# BackupPowerUnit.net
KiCad netlist of a schematic drawn in EAGLE
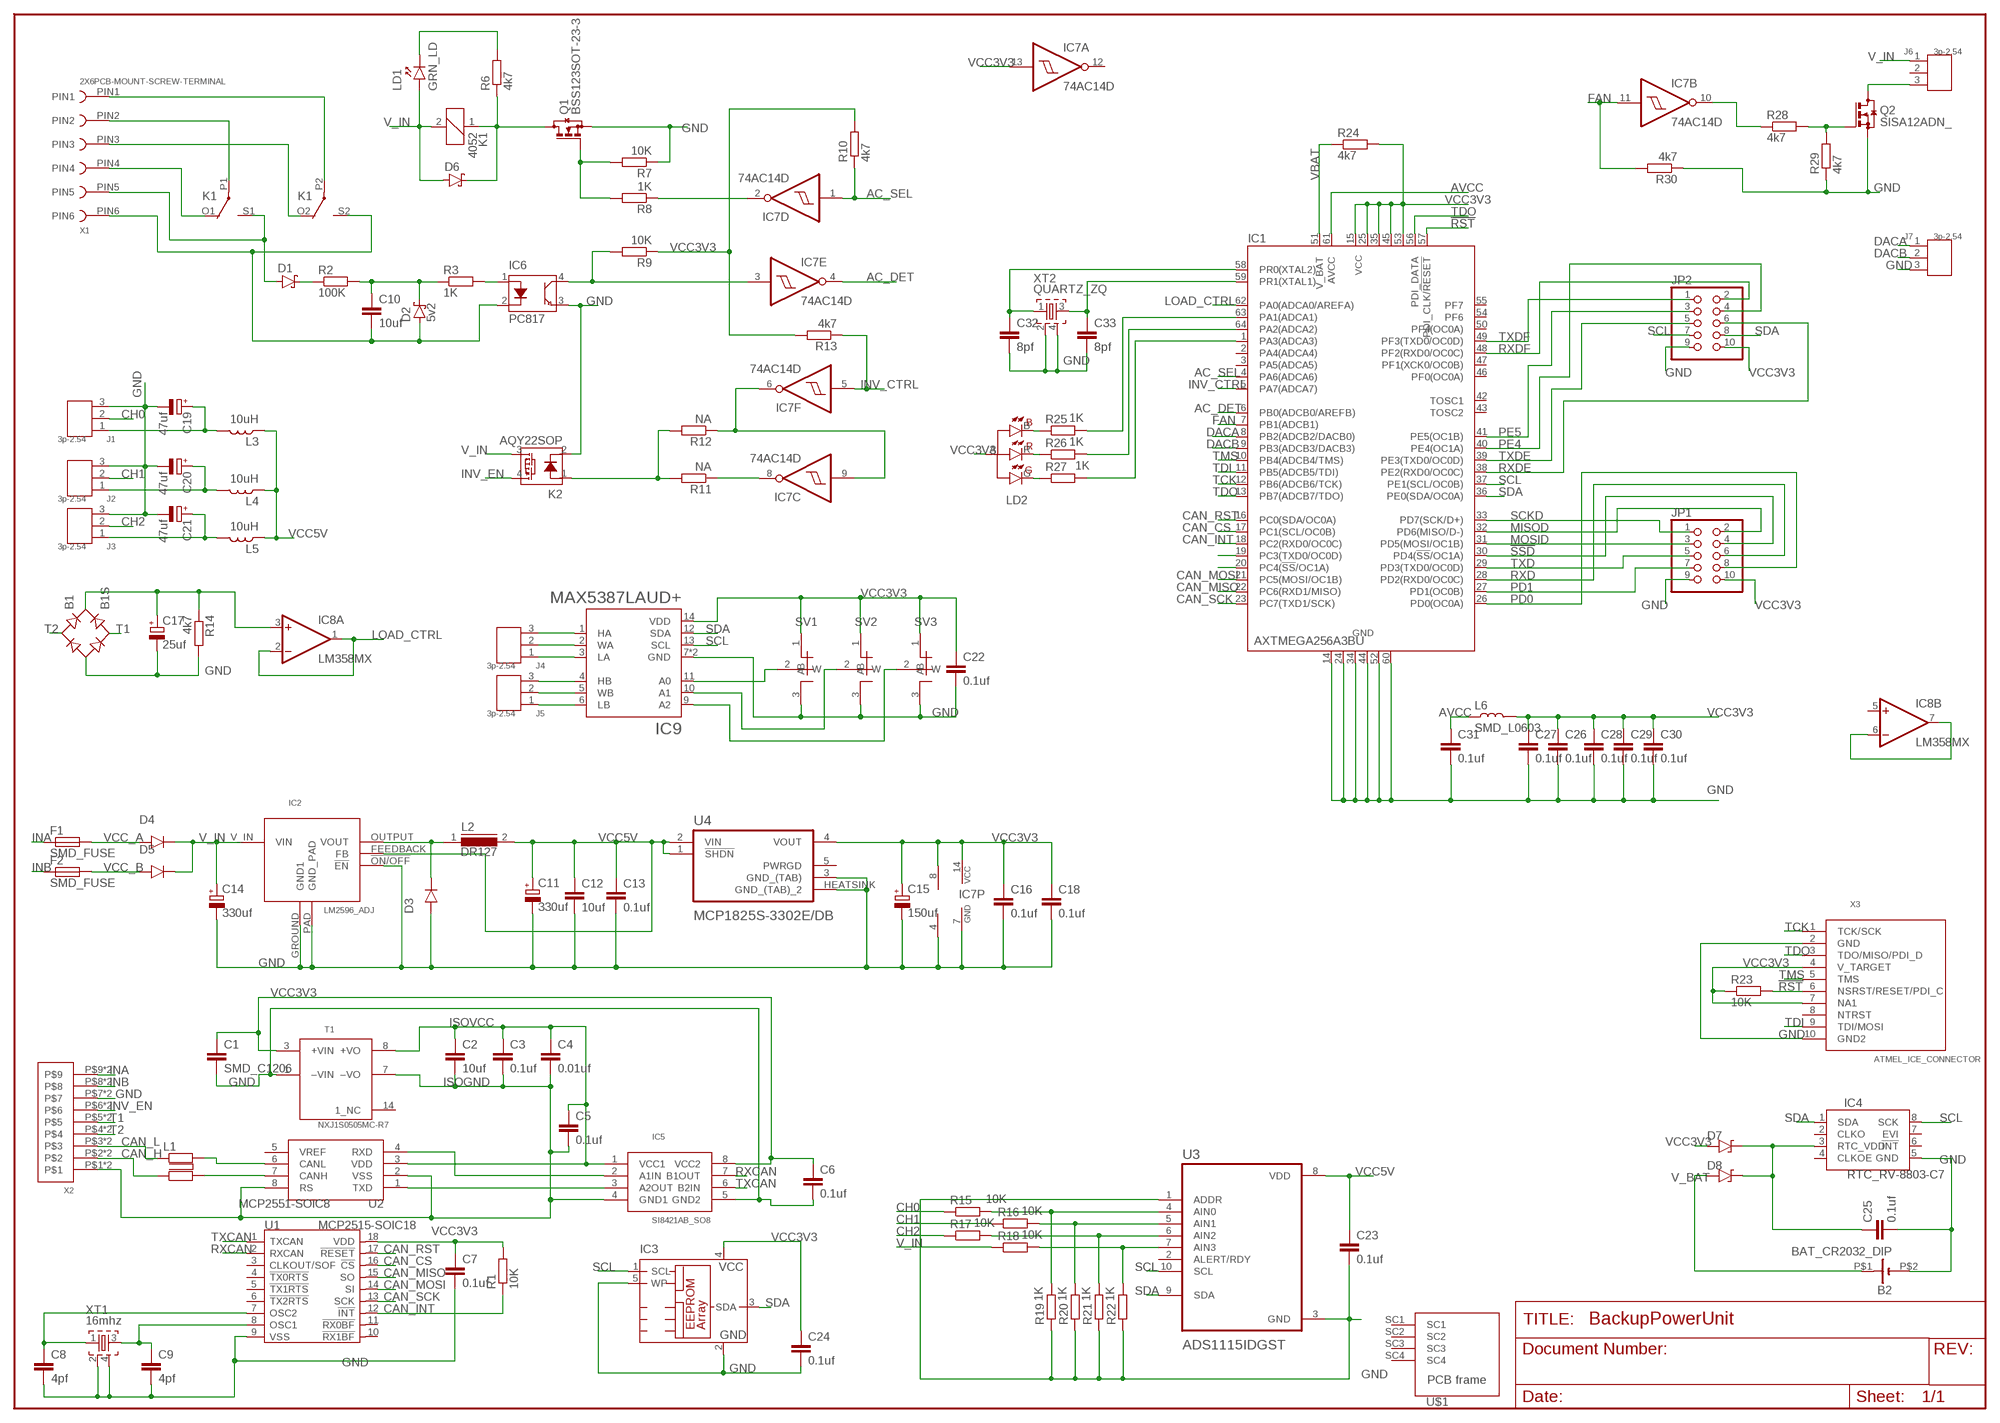
[diagram p0: schematic, sheet 1]

(export (version "E")
  (design (tool "Eeschema 10.0.6"))
  (components
    (comp (ref "B1")
      (value "B1S")
      (footprint "eagle-import:MBS")
      (libsource (lib "eagle-import") (part "BS1"))
    )
    (comp (ref "B2")
      (value "BAT_CR2032_DIP")
      (footprint "eagle-import:CR2032_DIP")
      (libsource (lib "eagle-import") (part "BAT_CR2032_DIP"))
    )
    (comp (ref "C1")
      (value "SMD_C1206")
      (footprint "eagle-import:1206")
      (libsource (lib "eagle-import") (part "SMD_C1206"))
    )
    (comp (ref "C2")
      (value "10uf")
      (footprint "eagle-import:1206")
      (libsource (lib "eagle-import") (part "SMD_C1206"))
    )
    (comp (ref "C3")
      (value "0.1uf")
      (footprint "eagle-import:0603")
      (libsource (lib "eagle-import") (part "SMD_C0603"))
    )
    (comp (ref "C4")
      (value "0.01uf")
      (footprint "eagle-import:0603")
      (libsource (lib "eagle-import") (part "SMD_C0603"))
    )
    (comp (ref "C5")
      (value "0.1uf")
      (footprint "eagle-import:0603")
      (libsource (lib "eagle-import") (part "SMD_C0603"))
    )
    (comp (ref "C6")
      (value "0.1uf")
      (footprint "eagle-import:0603")
      (libsource (lib "eagle-import") (part "SMD_C0603"))
    )
    (comp (ref "C7")
      (value "0.1uf")
      (footprint "eagle-import:0603")
      (libsource (lib "eagle-import") (part "SMD_C0603"))
    )
    (comp (ref "C8")
      (value "4pf")
      (footprint "eagle-import:0603")
      (libsource (lib "eagle-import") (part "SMD_C0603"))
    )
    (comp (ref "C9")
      (value "4pf")
      (footprint "eagle-import:0603")
      (libsource (lib "eagle-import") (part "SMD_C0603"))
    )
    (comp (ref "C10")
      (value "10uf")
      (footprint "eagle-import:0805")
      (libsource (lib "eagle-import") (part "SMD_C0805"))
    )
    (comp (ref "C11")
      (value "330uf")
      (footprint "eagle-import:3.6MM")
      (libsource (lib "eagle-import") (part "RADIAL_330UF_25V_8MM"))
    )
    (comp (ref "C12")
      (value "10uf")
      (footprint "eagle-import:1206")
      (libsource (lib "eagle-import") (part "SMD_C1206"))
    )
    (comp (ref "C13")
      (value "0.1uf")
      (footprint "eagle-import:0603")
      (libsource (lib "eagle-import") (part "SMD_C0603"))
    )
    (comp (ref "C14")
      (value "330uf")
      (footprint "eagle-import:3.6MM")
      (libsource (lib "eagle-import") (part "RADIAL_330UF_25V_8MM"))
    )
    (comp (ref "C15")
      (value "150uf")
      (footprint "eagle-import:KA-3528ASYC")
      (libsource (lib "eagle-import") (part "TANTAL_150UF_3528"))
    )
    (comp (ref "C16")
      (value "0.1uf")
      (footprint "eagle-import:0603")
      (libsource (lib "eagle-import") (part "SMD_C0603"))
    )
    (comp (ref "C17")
      (value "25uf")
      (footprint "eagle-import:KA-3528ASYC")
      (libsource (lib "eagle-import") (part "TANTAL_150UF_3528"))
    )
    (comp (ref "C18")
      (value "0.1uf")
      (footprint "eagle-import:0603")
      (libsource (lib "eagle-import") (part "SMD_C0603"))
    )
    (comp (ref "C19")
      (value "47uf")
      (footprint "eagle-import:KA-3528ASYC")
      (libsource (lib "eagle-import") (part "TANTAL_150UF_3528"))
    )
    (comp (ref "C20")
      (value "47uf")
      (footprint "eagle-import:KA-3528ASYC")
      (libsource (lib "eagle-import") (part "TANTAL_150UF_3528"))
    )
    (comp (ref "C21")
      (value "47uf")
      (footprint "eagle-import:KA-3528ASYC")
      (libsource (lib "eagle-import") (part "TANTAL_150UF_3528"))
    )
    (comp (ref "C22")
      (value "0.1uf")
      (footprint "eagle-import:0603")
      (libsource (lib "eagle-import") (part "SMD_C0603"))
    )
    (comp (ref "C23")
      (value "0.1uf")
      (footprint "eagle-import:0603")
      (libsource (lib "eagle-import") (part "SMD_C0603"))
    )
    (comp (ref "C24")
      (value "0.1uf")
      (footprint "eagle-import:0603")
      (libsource (lib "eagle-import") (part "SMD_C0603"))
    )
    (comp (ref "C25")
      (value "0.1uf")
      (footprint "eagle-import:0603")
      (libsource (lib "eagle-import") (part "SMD_C0603"))
    )
    (comp (ref "C26")
      (value "0.1uf")
      (footprint "eagle-import:0603")
      (libsource (lib "eagle-import") (part "SMD_C0603"))
    )
    (comp (ref "C27")
      (value "0.1uf")
      (footprint "eagle-import:0603")
      (libsource (lib "eagle-import") (part "SMD_C0603"))
    )
    (comp (ref "C28")
      (value "0.1uf")
      (footprint "eagle-import:0603")
      (libsource (lib "eagle-import") (part "SMD_C0603"))
    )
    (comp (ref "C29")
      (value "0.1uf")
      (footprint "eagle-import:0603")
      (libsource (lib "eagle-import") (part "SMD_C0603"))
    )
    (comp (ref "C30")
      (value "0.1uf")
      (footprint "eagle-import:0603")
      (libsource (lib "eagle-import") (part "SMD_C0603"))
    )
    (comp (ref "C31")
      (value "0.1uf")
      (footprint "eagle-import:0603")
      (libsource (lib "eagle-import") (part "SMD_C0603"))
    )
    (comp (ref "C32")
      (value "8pf")
      (footprint "eagle-import:0603")
      (libsource (lib "eagle-import") (part "SMD_C0603"))
    )
    (comp (ref "C33")
      (value "8pf")
      (footprint "eagle-import:0603")
      (libsource (lib "eagle-import") (part "SMD_C0603"))
    )
    (comp (ref "D1")
      (value "1N5819-B")
      (footprint "eagle-import:DO41-7.6")
      (libsource (lib "eagle-import") (part "1N5819-B"))
    )
    (comp (ref "D2")
      (value "5v2")
      (footprint "eagle-import:DO41-7.6")
      (libsource (lib "eagle-import") (part "1N5819-B"))
    )
    (comp (ref "D3")
      (value "D_MBRA340G")
      (footprint "eagle-import:SMA403D")
      (libsource (lib "eagle-import") (part "D_MBRA340G"))
    )
    (comp (ref "D4")
      (value "D_MBRA340G")
      (footprint "eagle-import:SMA403D")
      (libsource (lib "eagle-import") (part "D_MBRA340G"))
    )
    (comp (ref "D5")
      (value "D_MBRA340G")
      (footprint "eagle-import:SMA403D")
      (libsource (lib "eagle-import") (part "D_MBRA340G"))
    )
    (comp (ref "D6")
      (value "1N5819-B")
      (footprint "eagle-import:DO41-7.6")
      (libsource (lib "eagle-import") (part "1N5819-B"))
    )
    (comp (ref "D7")
      (value "D_SOD323")
      (footprint "eagle-import:SOD-323_D")
      (libsource (lib "eagle-import") (part "D_SOD323"))
    )
    (comp (ref "D8")
      (value "D_SOD323")
      (footprint "eagle-import:SOD-323_D")
      (libsource (lib "eagle-import") (part "D_SOD323"))
    )
    (comp (ref "F1")
      (value "SMD_FUSE")
      (footprint "eagle-import:SMD_2410_FUSE_NOK")
      (libsource (lib "eagle-import") (part "SMD_FUSE"))
    )
    (comp (ref "F2")
      (value "SMD_FUSE")
      (footprint "eagle-import:SMD_2410_FUSE_NOK")
      (libsource (lib "eagle-import") (part "SMD_FUSE"))
    )
    (comp (ref "IC1")
      (value "AXTMEGA256A3BU")
      (footprint "eagle-import:TQFP64")
      (libsource (lib "eagle-import") (part "AXTMEGA256A3BU"))
    )
    (comp (ref "IC2")
      (value "LM2596_ADJ")
      (footprint "eagle-import:DDPAK_TO-263(S)")
      (libsource (lib "eagle-import") (part "LM2596_ADJ"))
    )
    (comp (ref "IC3")
      (value "MICROCHIP-24AA01T-I/OT")
      (footprint "eagle-import:SOT-23(5)")
      (libsource (lib "eagle-import") (part "MICROCHIP-24AA01T-I/OT"))
    )
    (comp (ref "IC4")
      (value "RTC_RV-8803-C7")
      (footprint "eagle-import:C7_RTC")
      (libsource (lib "eagle-import") (part "RTC_RV-8803-C7"))
    )
    (comp (ref "IC5")
      (value "SI8421AB_SO8")
      (footprint "eagle-import:SO8")
      (libsource (lib "eagle-import") (part "SI8421AB_SO8"))
    )
    (comp (ref "IC6")
      (value "PC817")
      (footprint "eagle-import:DIL4-SMD")
      (libsource (lib "eagle-import") (part "PC817"))
    )
    (comp (ref "IC7")
      (value "74AC14D")
      (footprint "eagle-import:SO14")
      (libsource (lib "eagle-import") (part "7414DAC"))
    )
    (comp (ref "IC8")
      (value "LM358MX")
      (footprint "eagle-import:SO08")
      (libsource (lib "eagle-import") (part "LM358MX"))
    )
    (comp (ref "IC9")
      (value "MAX5387LAUD+")
      (footprint "eagle-import:SOP65P640X110-14N")
      (libsource (lib "eagle-import") (part "MAX5387LAUD+"))
    )
    (comp (ref "J1")
      (value "3p-2.54")
      (footprint "eagle-import:H3-2.54-7.62X5.8MM")
      (fields (field (name "MPN") "MC34631"))
      (libsource (lib "eagle-import") (part "DIP-MALE-JST(3P-2.54)"))
    )
    (comp (ref "J2")
      (value "3p-2.54")
      (footprint "eagle-import:H3-2.54-7.62X5.8MM")
      (fields (field (name "MPN") "MC34631"))
      (libsource (lib "eagle-import") (part "DIP-MALE-JST(3P-2.54)"))
    )
    (comp (ref "J3")
      (value "3p-2.54")
      (footprint "eagle-import:H3-2.54-7.62X5.8MM")
      (fields (field (name "MPN") "MC34631"))
      (libsource (lib "eagle-import") (part "DIP-MALE-JST(3P-2.54)"))
    )
    (comp (ref "J4")
      (value "3p-2.54")
      (footprint "eagle-import:H3-2.54-7.62X5.8MM")
      (fields (field (name "MPN") "MC34631"))
      (libsource (lib "eagle-import") (part "DIP-MALE-JST(3P-2.54)"))
    )
    (comp (ref "J5")
      (value "3p-2.54")
      (footprint "eagle-import:H3-2.54-7.62X5.8MM")
      (fields (field (name "MPN") "MC34631"))
      (libsource (lib "eagle-import") (part "DIP-MALE-JST(3P-2.54)"))
    )
    (comp (ref "J6")
      (value "3p-2.54")
      (footprint "eagle-import:H3-2.54-7.62X5.8MM")
      (fields (field (name "MPN") "MC34631"))
      (libsource (lib "eagle-import") (part "DIP-MALE-JST(3P-2.54)"))
    )
    (comp (ref "J7")
      (value "3p-2.54")
      (footprint "eagle-import:H3-2.54-7.62X5.8MM")
      (fields (field (name "MPN") "MC34631"))
      (libsource (lib "eagle-import") (part "DIP-MALE-JST(3P-2.54)"))
    )
    (comp (ref "JP1")
      (value "PINHD-2X5")
      (footprint "eagle-import:2X05")
      (libsource (lib "eagle-import") (part "PINHD-2X5"))
    )
    (comp (ref "JP2")
      (value "PINHD-2X5")
      (footprint "eagle-import:2X05")
      (libsource (lib "eagle-import") (part "PINHD-2X5"))
    )
    (comp (ref "K1")
      (value "4052")
      (footprint "eagle-import:F4052")
      (libsource (lib "eagle-import") (part "4052"))
    )
    (comp (ref "K2")
      (value "AQY22SOP")
      (footprint "eagle-import:SOP04")
      (libsource (lib "eagle-import") (part "AQYSOP22"))
    )
    (comp (ref "L1")
      (value "EPCOS_B82793_FILTER")
      (footprint "eagle-import:EPCOS_FILTER")
      (libsource (lib "eagle-import") (part "EPCOS_B82793_FILTER"))
    )
    (comp (ref "L2")
      (value "DR127")
      (footprint "eagle-import:DR127")
      (libsource (lib "eagle-import") (part "DR127"))
    )
    (comp (ref "L3")
      (value "10uH")
      (footprint "eagle-import:0603")
      (libsource (lib "eagle-import") (part "SMD_L0603"))
    )
    (comp (ref "L4")
      (value "10uH")
      (footprint "eagle-import:0603")
      (libsource (lib "eagle-import") (part "SMD_L0603"))
    )
    (comp (ref "L5")
      (value "10uH")
      (footprint "eagle-import:0603")
      (libsource (lib "eagle-import") (part "SMD_L0603"))
    )
    (comp (ref "L6")
      (value "SMD_L0603")
      (footprint "eagle-import:0603")
      (libsource (lib "eagle-import") (part "SMD_L0603"))
    )
    (comp (ref "LD1")
      (value "GRN_LD")
      (footprint "eagle-import:0603_P")
      (libsource (lib "eagle-import") (part "LED0603"))
    )
    (comp (ref "LD2")
      (value "LTSN-N213EGBW(RGB_LED)")
      (footprint "eagle-import:LTSN-N213EGBW")
      (libsource (lib "eagle-import") (part "LTSN-N213EGBW(RGB_LED)"))
    )
    (comp (ref "Q1")
      (value "BSS123SOT-23-3")
      (footprint "eagle-import:SOT-23(3)")
      (libsource (lib "eagle-import") (part "BSS123SOT-23-3"))
    )
    (comp (ref "Q2")
      (value "SISA12ADN_")
      (footprint "eagle-import:VISHAY_SIS468DN-T1-GE3")
      (libsource (lib "eagle-import") (part "SISA12ADN_"))
    )
    (comp (ref "R1")
      (value "10K")
      (footprint "eagle-import:0603")
      (libsource (lib "eagle-import") (part "SMD_R0603"))
    )
    (comp (ref "R2")
      (value "100K")
      (footprint "eagle-import:0204_7")
      (libsource (lib "eagle-import") (part "R-EU_0204/7"))
    )
    (comp (ref "R3")
      (value "1K")
      (footprint "eagle-import:0603")
      (libsource (lib "eagle-import") (part "SMD_R0603"))
    )
    (comp (ref "R6")
      (value "4k7")
      (footprint "eagle-import:0603")
      (libsource (lib "eagle-import") (part "SMD_R0603"))
    )
    (comp (ref "R7")
      (value "10K")
      (footprint "eagle-import:0603")
      (libsource (lib "eagle-import") (part "SMD_R0603"))
    )
    (comp (ref "R8")
      (value "1K")
      (footprint "eagle-import:0603")
      (libsource (lib "eagle-import") (part "SMD_R0603"))
    )
    (comp (ref "R9")
      (value "10K")
      (footprint "eagle-import:0603")
      (libsource (lib "eagle-import") (part "SMD_R0603"))
    )
    (comp (ref "R10")
      (value "4k7")
      (footprint "eagle-import:0603")
      (libsource (lib "eagle-import") (part "SMD_R0603"))
    )
    (comp (ref "R11")
      (value "NA")
      (footprint "eagle-import:0603")
      (libsource (lib "eagle-import") (part "SMD_R0603"))
    )
    (comp (ref "R12")
      (value "NA")
      (footprint "eagle-import:0603")
      (libsource (lib "eagle-import") (part "SMD_R0603"))
    )
    (comp (ref "R13")
      (value "4k7")
      (footprint "eagle-import:0603")
      (libsource (lib "eagle-import") (part "SMD_R0603"))
    )
    (comp (ref "R14")
      (value "4k7")
      (footprint "eagle-import:0603")
      (libsource (lib "eagle-import") (part "SMD_R0603"))
    )
    (comp (ref "R15")
      (value "10K")
      (footprint "eagle-import:0603")
      (libsource (lib "eagle-import") (part "SMD_R0603"))
    )
    (comp (ref "R16")
      (value "10K")
      (footprint "eagle-import:0603")
      (libsource (lib "eagle-import") (part "SMD_R0603"))
    )
    (comp (ref "R17")
      (value "10K")
      (footprint "eagle-import:0603")
      (libsource (lib "eagle-import") (part "SMD_R0603"))
    )
    (comp (ref "R18")
      (value "10K")
      (footprint "eagle-import:0603")
      (libsource (lib "eagle-import") (part "SMD_R0603"))
    )
    (comp (ref "R19")
      (value "1K")
      (footprint "eagle-import:0603")
      (libsource (lib "eagle-import") (part "SMD_R0603"))
    )
    (comp (ref "R20")
      (value "1K")
      (footprint "eagle-import:0603")
      (libsource (lib "eagle-import") (part "SMD_R0603"))
    )
    (comp (ref "R21")
      (value "1K")
      (footprint "eagle-import:0603")
      (libsource (lib "eagle-import") (part "SMD_R0603"))
    )
    (comp (ref "R22")
      (value "1K")
      (footprint "eagle-import:0603")
      (libsource (lib "eagle-import") (part "SMD_R0603"))
    )
    (comp (ref "R23")
      (value "10K")
      (footprint "eagle-import:0603")
      (libsource (lib "eagle-import") (part "SMD_R0603"))
    )
    (comp (ref "R24")
      (value "4k7")
      (footprint "eagle-import:0603")
      (libsource (lib "eagle-import") (part "SMD_R0603"))
    )
    (comp (ref "R25")
      (value "1K")
      (footprint "eagle-import:0603")
      (libsource (lib "eagle-import") (part "SMD_R0603"))
    )
    (comp (ref "R26")
      (value "1K")
      (footprint "eagle-import:0603")
      (libsource (lib "eagle-import") (part "SMD_R0603"))
    )
    (comp (ref "R27")
      (value "1K")
      (footprint "eagle-import:0603")
      (libsource (lib "eagle-import") (part "SMD_R0603"))
    )
    (comp (ref "R28")
      (value "4k7")
      (footprint "eagle-import:0603")
      (libsource (lib "eagle-import") (part "SMD_R0603"))
    )
    (comp (ref "R29")
      (value "4k7")
      (footprint "eagle-import:0603")
      (libsource (lib "eagle-import") (part "SMD_R0603"))
    )
    (comp (ref "R30")
      (value "4k7")
      (footprint "eagle-import:0603")
      (libsource (lib "eagle-import") (part "SMD_R0603"))
    )
    (comp (ref "SV1")
      (value "SMD_SWITCH_JUMPER")
      (footprint "eagle-import:0603_JUMP")
      (libsource (lib "eagle-import") (part "SMD_SWITCH_JUMPER"))
    )
    (comp (ref "SV2")
      (value "SMD_SWITCH_JUMPER")
      (footprint "eagle-import:0603_JUMP")
      (libsource (lib "eagle-import") (part "SMD_SWITCH_JUMPER"))
    )
    (comp (ref "SV3")
      (value "SMD_SWITCH_JUMPER")
      (footprint "eagle-import:0603_JUMP")
      (libsource (lib "eagle-import") (part "SMD_SWITCH_JUMPER"))
    )
    (comp (ref "T1")
      (value "NXJ1S0505MC-R7")
      (footprint "eagle-import:NXJ1SXXXXMC")
      (libsource (lib "eagle-import") (part "NXJ1S0505MC-R7"))
    )
    (comp (ref "U$1")
      (value "JLC_PCB_FRAME80X100_FRAME")
      (footprint "eagle-import:80X100_PCB_FRAME")
      (libsource (lib "eagle-import") (part "JLC_PCB_FRAME80X100_FRAME"))
    )
    (comp (ref "U1")
      (value "MCP2515-SOIC18")
      (footprint "eagle-import:SO18L")
      (libsource (lib "eagle-import") (part "MCP2515-SOIC18"))
    )
    (comp (ref "U2")
      (value "MCP2551-SOIC8")
      (footprint "eagle-import:SO8")
      (libsource (lib "eagle-import") (part "MCP2551-SOIC8"))
    )
    (comp (ref "U3")
      (value "ADS1115IDGST")
      (footprint "eagle-import:SOP50P490X110-10N")
      (fields (field (name "MF") "Texas Instruments"))
      (libsource (lib "eagle-import") (part "ADS1115IDGST"))
    )
    (comp (ref "U4")
      (value "MCP1825S-3302E/DB")
      (footprint "eagle-import:SOT230P700X180-4N")
      (fields (field (name "MF") "Microchip"))
      (libsource (lib "eagle-import") (part "MCP1825S-3302E/DB"))
    )
    (comp (ref "X1")
      (value "2X6PCB-MOUNT-SCREW-TERMINAL")
      (footprint "eagle-import:2X6PCB-MOUNT-SCREW-TERMINAL")
      (libsource (lib "eagle-import") (part "2X6PCB-MOUNT-SCREW-TERMINAL"))
    )
    (comp (ref "X2")
      (value "WAGO250_X9")
      (footprint "eagle-import:WAGO250_FP_9X")
      (libsource (lib "eagle-import") (part "WAGO250_X9"))
    )
    (comp (ref "X3")
      (value "ATMEL_ICE_CONNECTOR")
      (footprint "eagle-import:MINI10P_SPI_JTAG_PDI")
      (libsource (lib "eagle-import") (part "ATMEL_ICE_CONNECTOR"))
    )
    (comp (ref "XT1")
      (value "16mhz")
      (footprint "eagle-import:QUARTZ_3X3MM")
      (libsource (lib "eagle-import") (part "QUARTZ_ZQ"))
    )
    (comp (ref "XT2")
      (value "QUARTZ_ZQ")
      (footprint "eagle-import:QUARTZ_3X3MM")
      (libsource (lib "eagle-import") (part "QUARTZ_ZQ"))
    )
  )
  (nets
    (net (code "1") (name "/AC_DET") (class "Default")
      (node (ref "IC1") (pin "6") (pinfunction "PB0(ADCB0/AREFB)_6") (pintype "bidirectional"))
      (node (ref "IC7") (pin "4") (pinfunction "O_4") (pintype "output"))
    )
    (net (code "2") (name "/AC_SEL") (class "Default")
      (node (ref "IC1") (pin "4") (pinfunction "PA6(ADCA6)_4") (pintype "bidirectional"))
      (node (ref "IC7") (pin "1") (pinfunction "I_1") (pintype "input"))
      (node (ref "R10") (pin "1") (pinfunction "1_1") (pintype "passive"))
    )
    (net (code "3") (name "/AVCC") (class "Default")
      (node (ref "C31") (pin "1") (pinfunction "1_1") (pintype "passive"))
      (node (ref "IC1") (pin "61") (pinfunction "AVCC_61") (pintype "input"))
      (node (ref "L6") (pin "1") (pinfunction "1_1") (pintype "passive"))
    )
    (net (code "4") (name "/CAN_CS") (class "Default")
      (node (ref "IC1") (pin "17") (pinfunction "PC1(SCL/OC0B)_17") (pintype "bidirectional"))
      (node (ref "U1") (pin "16") (pinfunction "~{CS}_16") (pintype "input"))
    )
    (net (code "5") (name "/CAN_H") (class "Default")
      (node (ref "L1") (pin "P$2") (pinfunction "2_P$2") (pintype "passive"))
      (node (ref "X2") (pin "P$2") (pinfunction "P$2_P$2") (pintype "bidirectional"))
      (node (ref "X2") (pin "U$2") (pinfunction "P$2_U$2") (pintype "bidirectional"))
    )
    (net (code "6") (name "/CAN_INT") (class "Default")
      (node (ref "IC1") (pin "18") (pinfunction "PC2(RXD0/OC0C)_18") (pintype "bidirectional"))
      (node (ref "R1") (pin "1") (pinfunction "1_1") (pintype "passive"))
      (node (ref "U1") (pin "12") (pinfunction "~{INT}_12") (pintype "output"))
    )
    (net (code "7") (name "/CAN_L") (class "Default")
      (node (ref "L1") (pin "P$1") (pinfunction "1_P$1") (pintype "passive"))
      (node (ref "X2") (pin "P$3") (pinfunction "P$3_P$3") (pintype "bidirectional"))
      (node (ref "X2") (pin "U$3") (pinfunction "P$3_U$3") (pintype "bidirectional"))
    )
    (net (code "8") (name "/CAN_MISO") (class "Default")
      (node (ref "IC1") (pin "22") (pinfunction "PC6(RXD1/MISO)_22") (pintype "bidirectional"))
      (node (ref "U1") (pin "15") (pinfunction "SO_15") (pintype "output"))
    )
    (net (code "9") (name "/CAN_MOSI") (class "Default")
      (node (ref "IC1") (pin "21") (pinfunction "PC5(MOSI/OC1B)_21") (pintype "bidirectional"))
      (node (ref "U1") (pin "14") (pinfunction "SI_14") (pintype "input"))
    )
    (net (code "10") (name "/CAN_RST") (class "Default")
      (node (ref "IC1") (pin "16") (pinfunction "PC0(SDA/OC0A)_16") (pintype "bidirectional"))
      (node (ref "U1") (pin "17") (pinfunction "~{RESET}_17") (pintype "input"))
    )
    (net (code "11") (name "/CAN_SCK") (class "Default")
      (node (ref "IC1") (pin "23") (pinfunction "PC7(TXD1/SCK)_23") (pintype "bidirectional"))
      (node (ref "U1") (pin "13") (pinfunction "SCK_13") (pintype "input"))
    )
    (net (code "12") (name "/CH0") (class "Default")
      (node (ref "J1") (pin "2") (pinfunction "P$2_2") (pintype "bidirectional"))
      (node (ref "R15") (pin "1") (pinfunction "1_1") (pintype "passive"))
    )
    (net (code "13") (name "/CH1") (class "Default")
      (node (ref "J2") (pin "2") (pinfunction "P$2_2") (pintype "bidirectional"))
      (node (ref "R16") (pin "1") (pinfunction "1_1") (pintype "passive"))
    )
    (net (code "14") (name "/CH2") (class "Default")
      (node (ref "J3") (pin "2") (pinfunction "P$2_2") (pintype "bidirectional"))
      (node (ref "R17") (pin "1") (pinfunction "1_1") (pintype "passive"))
    )
    (net (code "15") (name "/DACA") (class "Default")
      (node (ref "IC1") (pin "8") (pinfunction "PB2(ADCB2/DACB0)_8") (pintype "bidirectional"))
      (node (ref "J7") (pin "1") (pinfunction "P$1_1") (pintype "bidirectional"))
    )
    (net (code "16") (name "/DACB") (class "Default")
      (node (ref "IC1") (pin "9") (pinfunction "PB3(ADCB3/DACB3)_9") (pintype "bidirectional"))
      (node (ref "J7") (pin "2") (pinfunction "P$2_2") (pintype "bidirectional"))
    )
    (net (code "17") (name "/FAN") (class "Default")
      (node (ref "IC1") (pin "7") (pinfunction "PB1(ADCB1)_7") (pintype "bidirectional"))
      (node (ref "IC7") (pin "11") (pinfunction "I_11") (pintype "input"))
      (node (ref "R30") (pin "2") (pinfunction "2_2") (pintype "passive"))
    )
    (net (code "18") (name "/GND") (class "Default")
      (node (ref "B1") (pin "-") (pinfunction "-_-") (pintype "passive"))
      (node (ref "B2") (pin "P$2") (pinfunction "-_P$2") (pintype "passive"))
      (node (ref "C1") (pin "2") (pinfunction "2_2") (pintype "passive"))
      (node (ref "C11") (pin "P$1") (pinfunction "-_P$1") (pintype "passive"))
      (node (ref "C12") (pin "2") (pinfunction "2_2") (pintype "passive"))
      (node (ref "C13") (pin "2") (pinfunction "2_2") (pintype "passive"))
      (node (ref "C14") (pin "P$1") (pinfunction "-_P$1") (pintype "passive"))
      (node (ref "C15") (pin "M") (pinfunction "-_M") (pintype "passive"))
      (node (ref "C16") (pin "2") (pinfunction "2_2") (pintype "passive"))
      (node (ref "C17") (pin "M") (pinfunction "-_M") (pintype "passive"))
      (node (ref "C18") (pin "2") (pinfunction "2_2") (pintype "passive"))
      (node (ref "C19") (pin "M") (pinfunction "-_M") (pintype "passive"))
      (node (ref "C20") (pin "M") (pinfunction "-_M") (pintype "passive"))
      (node (ref "C21") (pin "M") (pinfunction "-_M") (pintype "passive"))
      (node (ref "C22") (pin "2") (pinfunction "2_2") (pintype "passive"))
      (node (ref "C23") (pin "2") (pinfunction "2_2") (pintype "passive"))
      (node (ref "C24") (pin "2") (pinfunction "2_2") (pintype "passive"))
      (node (ref "C25") (pin "2") (pinfunction "2_2") (pintype "passive"))
      (node (ref "C26") (pin "2") (pinfunction "2_2") (pintype "passive"))
      (node (ref "C27") (pin "2") (pinfunction "2_2") (pintype "passive"))
      (node (ref "C28") (pin "2") (pinfunction "2_2") (pintype "passive"))
      (node (ref "C29") (pin "2") (pinfunction "2_2") (pintype "passive"))
      (node (ref "C30") (pin "2") (pinfunction "2_2") (pintype "passive"))
      (node (ref "C31") (pin "2") (pinfunction "2_2") (pintype "passive"))
      (node (ref "C32") (pin "2") (pinfunction "2_2") (pintype "passive"))
      (node (ref "C33") (pin "2") (pinfunction "2_2") (pintype "passive"))
      (node (ref "C6") (pin "2") (pinfunction "2_2") (pintype "passive"))
      (node (ref "C7") (pin "2") (pinfunction "2_2") (pintype "passive"))
      (node (ref "C8") (pin "2") (pinfunction "2_2") (pintype "passive"))
      (node (ref "C9") (pin "2") (pinfunction "2_2") (pintype "passive"))
      (node (ref "D3") (pin "P$2") (pinfunction "A_P$2") (pintype "bidirectional"))
      (node (ref "IC1") (pin "14") (pinfunction "GND1_14") (pintype "power_in"))
      (node (ref "IC1") (pin "24") (pinfunction "GND2_24") (pintype "power_in"))
      (node (ref "IC1") (pin "34") (pinfunction "GND3_34") (pintype "power_in"))
      (node (ref "IC1") (pin "44") (pinfunction "GND4_44") (pintype "power_in"))
      (node (ref "IC1") (pin "52") (pinfunction "GND5_52") (pintype "power_in"))
      (node (ref "IC1") (pin "60") (pinfunction "GND6_60") (pintype "power_in"))
      (node (ref "IC2") (pin "!ON/OFF") (pinfunction "~{EN}_!ON/OFF") (pintype "input"))
      (node (ref "IC2") (pin "GROUND") (pinfunction "GND1_GROUND") (pintype "power_in"))
      (node (ref "IC2") (pin "PAD") (pinfunction "GND_PAD_PAD") (pintype "power_in"))
      (node (ref "IC3") (pin "2") (pinfunction "GND_2") (pintype "power_in"))
      (node (ref "IC3") (pin "5") (pinfunction "WP_5") (pintype "input"))
      (node (ref "IC4") (pin "5") (pinfunction "GND_5") (pintype "bidirectional"))
      (node (ref "IC5") (pin "5") (pinfunction "GND2_5") (pintype "bidirectional"))
      (node (ref "IC6") (pin "3") (pinfunction "E_3") (pintype "passive"))
      (node (ref "IC7") (pin "7") (pinfunction "GND_7") (pintype "power_in"))
      (node (ref "IC8") (pin "4") (pinfunction "V-_4") (pintype "power_in"))
      (node (ref "IC9") (pin "7") (pinfunction "GND_7") (pintype "bidirectional"))
      (node (ref "IC9") (pin "8") (pinfunction "GND_8") (pintype "bidirectional"))
      (node (ref "J1") (pin "3") (pinfunction "P$3_3") (pintype "bidirectional"))
      (node (ref "J2") (pin "3") (pinfunction "P$3_3") (pintype "bidirectional"))
      (node (ref "J3") (pin "3") (pinfunction "P$3_3") (pintype "bidirectional"))
      (node (ref "J7") (pin "3") (pinfunction "P$3_3") (pintype "bidirectional"))
      (node (ref "JP1") (pin "9") (pinfunction "9_9") (pintype "passive"))
      (node (ref "JP2") (pin "9") (pinfunction "9_9") (pintype "passive"))
      (node (ref "K2") (pin "2") (pinfunction "K_2") (pintype "passive"))
      (node (ref "Q1") (pin "2") (pinfunction "S_2") (pintype "passive"))
      (node (ref "Q2") (pin "1") (pinfunction "S_1") (pintype "passive"))
      (node (ref "Q2") (pin "2") (pinfunction "S_2") (pintype "passive"))
      (node (ref "Q2") (pin "3") (pinfunction "S_3") (pintype "passive"))
      (node (ref "R14") (pin "2") (pinfunction "2_2") (pintype "passive"))
      (node (ref "R19") (pin "1") (pinfunction "1_1") (pintype "passive"))
      (node (ref "R20") (pin "1") (pinfunction "1_1") (pintype "passive"))
      (node (ref "R21") (pin "1") (pinfunction "1_1") (pintype "passive"))
      (node (ref "R22") (pin "1") (pinfunction "1_1") (pintype "passive"))
      (node (ref "R29") (pin "1") (pinfunction "1_1") (pintype "passive"))
      (node (ref "R30") (pin "1") (pinfunction "1_1") (pintype "passive"))
      (node (ref "R7") (pin "1") (pinfunction "1_1") (pintype "passive"))
      (node (ref "SV1") (pin "3") (pinfunction "B_3") (pintype "bidirectional"))
      (node (ref "SV2") (pin "3") (pinfunction "B_3") (pintype "bidirectional"))
      (node (ref "SV3") (pin "3") (pinfunction "B_3") (pintype "bidirectional"))
      (node (ref "T1") (pin "1") (pinfunction "–VIN_1") (pintype "power_in"))
      (node (ref "U1") (pin "9") (pinfunction "VSS_9") (pintype "power_in"))
      (node (ref "U3") (pin "1") (pinfunction "ADDR_1") (pintype "input"))
      (node (ref "U3") (pin "3") (pinfunction "GND_3") (pintype "power_in"))
      (node (ref "U4") (pin "3") (pinfunction "GND_(TAB)_3") (pintype "power_in"))
      (node (ref "U4") (pin "HEATSINK") (pinfunction "GND_(TAB)_2_HEATSINK") (pintype "power_in"))
      (node (ref "X2") (pin "P$7") (pinfunction "P$7_P$7") (pintype "bidirectional"))
      (node (ref "X2") (pin "U$7") (pinfunction "P$7_U$7") (pintype "bidirectional"))
      (node (ref "X3") (pin "10") (pinfunction "GND2_10") (pintype "bidirectional"))
      (node (ref "X3") (pin "2") (pinfunction "GND_2") (pintype "bidirectional"))
      (node (ref "XT1") (pin "2") (pinfunction "2_2") (pintype "passive"))
      (node (ref "XT1") (pin "4") (pinfunction "4_4") (pintype "passive"))
      (node (ref "XT2") (pin "2") (pinfunction "2_2") (pintype "passive"))
      (node (ref "XT2") (pin "4") (pinfunction "4_4") (pintype "passive"))
    )
    (net (code "19") (name "/INA") (class "Default")
      (node (ref "F1") (pin "P$1") (pinfunction "1_P$1") (pintype "passive"))
      (node (ref "X2") (pin "P$9") (pinfunction "P$9_P$9") (pintype "bidirectional"))
      (node (ref "X2") (pin "U$9") (pinfunction "P$9_U$9") (pintype "bidirectional"))
    )
    (net (code "20") (name "/INB") (class "Default")
      (node (ref "F2") (pin "P$1") (pinfunction "1_P$1") (pintype "passive"))
      (node (ref "X2") (pin "P$8") (pinfunction "P$8_P$8") (pintype "bidirectional"))
      (node (ref "X2") (pin "U$8") (pinfunction "P$8_U$8") (pintype "bidirectional"))
    )
    (net (code "21") (name "/INV_CTRL") (class "Default")
      (node (ref "IC1") (pin "5") (pinfunction "PA7(ADCA7)_5") (pintype "bidirectional"))
      (node (ref "IC7") (pin "5") (pinfunction "I_5") (pintype "input"))
      (node (ref "R13") (pin "1") (pinfunction "1_1") (pintype "passive"))
    )
    (net (code "22") (name "/INV_EN") (class "Default")
      (node (ref "K2") (pin "4") (pinfunction "DS1_4") (pintype "passive"))
      (node (ref "X2") (pin "P$6") (pinfunction "P$6_P$6") (pintype "bidirectional"))
      (node (ref "X2") (pin "U$6") (pinfunction "P$6_U$6") (pintype "bidirectional"))
    )
    (net (code "23") (name "/ISOGND") (class "Default")
      (node (ref "C2") (pin "2") (pinfunction "2_2") (pintype "passive"))
      (node (ref "C3") (pin "2") (pinfunction "2_2") (pintype "passive"))
      (node (ref "C4") (pin "2") (pinfunction "2_2") (pintype "passive"))
      (node (ref "C5") (pin "2") (pinfunction "2_2") (pintype "passive"))
      (node (ref "IC5") (pin "4") (pinfunction "GND1_4") (pintype "bidirectional"))
      (node (ref "T1") (pin "7") (pinfunction "–VO_7") (pintype "power_in"))
      (node (ref "U2") (pin "2") (pinfunction "VSS_2") (pintype "bidirectional"))
      (node (ref "U2") (pin "8") (pinfunction "RS_8") (pintype "bidirectional"))
      (node (ref "X2") (pin "P$1") (pinfunction "P$1_P$1") (pintype "bidirectional"))
      (node (ref "X2") (pin "U$1") (pinfunction "P$1_U$1") (pintype "bidirectional"))
    )
    (net (code "24") (name "/ISOVCC") (class "Default")
      (node (ref "C2") (pin "1") (pinfunction "1_1") (pintype "passive"))
      (node (ref "C3") (pin "1") (pinfunction "1_1") (pintype "passive"))
      (node (ref "C4") (pin "1") (pinfunction "1_1") (pintype "passive"))
      (node (ref "C5") (pin "1") (pinfunction "1_1") (pintype "passive"))
      (node (ref "IC5") (pin "1") (pinfunction "VCC1_1") (pintype "bidirectional"))
      (node (ref "T1") (pin "8") (pinfunction "+VO_8") (pintype "power_in"))
      (node (ref "U2") (pin "3") (pinfunction "VDD_3") (pintype "bidirectional"))
    )
    (net (code "25") (name "/LOAD_CTRL") (class "Default")
      (node (ref "IC1") (pin "62") (pinfunction "PA0(ADCA0/AREFA)_62") (pintype "bidirectional"))
      (node (ref "IC8") (pin "1") (pinfunction "OUT_1") (pintype "output"))
      (node (ref "IC8") (pin "2") (pinfunction "-IN_2") (pintype "input"))
    )
    (net (code "26") (name "/MISOD") (class "Default")
      (node (ref "IC1") (pin "32") (pinfunction "PD6(MISO/D-)_32") (pintype "bidirectional"))
      (node (ref "JP1") (pin "2") (pinfunction "2_2") (pintype "passive"))
    )
    (net (code "27") (name "/MOSID") (class "Default")
      (node (ref "IC1") (pin "31") (pinfunction "PD5(MOSI/OC1B)_31") (pintype "bidirectional"))
      (node (ref "JP1") (pin "3") (pinfunction "3_3") (pintype "passive"))
    )
    (net (code "28") (name "/PD0") (class "Default")
      (node (ref "IC1") (pin "26") (pinfunction "PD0(OC0A)_26") (pintype "bidirectional"))
      (node (ref "JP1") (pin "8") (pinfunction "8_8") (pintype "passive"))
    )
    (net (code "29") (name "/PD1") (class "Default")
      (node (ref "IC1") (pin "27") (pinfunction "PD1(OC0B)_27") (pintype "bidirectional"))
      (node (ref "JP1") (pin "7") (pinfunction "7_7") (pintype "passive"))
    )
    (net (code "30") (name "/PE4") (class "Default")
      (node (ref "IC1") (pin "40") (pinfunction "PE4(OC1A)_40") (pintype "bidirectional"))
      (node (ref "JP2") (pin "4") (pinfunction "4_4") (pintype "passive"))
    )
    (net (code "31") (name "/PE5") (class "Default")
      (node (ref "IC1") (pin "41") (pinfunction "PE5(OC1B)_41") (pintype "bidirectional"))
      (node (ref "JP2") (pin "3") (pinfunction "3_3") (pintype "passive"))
    )
    (net (code "32") (name "/RXCAN") (class "Default")
      (node (ref "IC5") (pin "7") (pinfunction "B1OUT_7") (pintype "bidirectional"))
      (node (ref "U1") (pin "2") (pinfunction "RXCAN_2") (pintype "input"))
    )
    (net (code "33") (name "/RXD") (class "Default")
      (node (ref "IC1") (pin "28") (pinfunction "PD2(RXD0/OC0C)_28") (pintype "bidirectional"))
      (node (ref "JP1") (pin "6") (pinfunction "6_6") (pintype "passive"))
    )
    (net (code "34") (name "/RXDE") (class "Default")
      (node (ref "IC1") (pin "38") (pinfunction "PE2(RXD0/OC0C)_38") (pintype "bidirectional"))
      (node (ref "JP2") (pin "6") (pinfunction "6_6") (pintype "passive"))
    )
    (net (code "35") (name "/RXDF") (class "Default")
      (node (ref "IC1") (pin "48") (pinfunction "PF2(RXD0/OC0C)_48") (pintype "bidirectional"))
      (node (ref "JP2") (pin "2") (pinfunction "2_2") (pintype "passive"))
    )
    (net (code "36") (name "/SCKD") (class "Default")
      (node (ref "IC1") (pin "33") (pinfunction "PD7(SCK/D+)_33") (pintype "bidirectional"))
      (node (ref "JP1") (pin "1") (pinfunction "1_1") (pintype "passive"))
    )
    (net (code "37") (name "/SCL") (class "Default")
      (node (ref "IC1") (pin "37") (pinfunction "PE1(SCL/OC0B)_37") (pintype "bidirectional"))
      (node (ref "IC3") (pin "1") (pinfunction "SCL_1") (pintype "input"))
      (node (ref "IC4") (pin "8") (pinfunction "SCK_8") (pintype "bidirectional"))
      (node (ref "IC9") (pin "13") (pinfunction "SCL_13") (pintype "bidirectional"))
      (node (ref "JP2") (pin "7") (pinfunction "7_7") (pintype "passive"))
      (node (ref "U3") (pin "10") (pinfunction "SCL_10") (pintype "input"))
    )
    (net (code "38") (name "/SDA") (class "Default")
      (node (ref "IC1") (pin "36") (pinfunction "PE0(SDA/OC0A)_36") (pintype "bidirectional"))
      (node (ref "IC3") (pin "3") (pinfunction "SDA_3") (pintype "bidirectional"))
      (node (ref "IC4") (pin "1") (pinfunction "SDA_1") (pintype "bidirectional"))
      (node (ref "IC9") (pin "12") (pinfunction "SDA_12") (pintype "bidirectional"))
      (node (ref "JP2") (pin "8") (pinfunction "8_8") (pintype "passive"))
      (node (ref "U3") (pin "9") (pinfunction "SDA_9") (pintype "bidirectional"))
    )
    (net (code "39") (name "/T1") (class "Default")
      (node (ref "B1") (pin "AC2") (pinfunction "AC2_AC2") (pintype "passive"))
      (node (ref "X2") (pin "P$5") (pinfunction "P$5_P$5") (pintype "bidirectional"))
      (node (ref "X2") (pin "U$5") (pinfunction "P$5_U$5") (pintype "bidirectional"))
    )
    (net (code "40") (name "/T2") (class "Default")
      (node (ref "B1") (pin "AC1") (pinfunction "AC1_AC1") (pintype "passive"))
      (node (ref "X2") (pin "P$4") (pinfunction "P$4_P$4") (pintype "bidirectional"))
      (node (ref "X2") (pin "U$4") (pinfunction "P$4_U$4") (pintype "bidirectional"))
    )
    (net (code "41") (name "/TCK") (class "Default")
      (node (ref "IC1") (pin "12") (pinfunction "PB6(ADCB6/TCK)_12") (pintype "bidirectional"))
      (node (ref "X3") (pin "1") (pinfunction "TCK/SCK_1") (pintype "bidirectional"))
    )
    (net (code "42") (name "/TDI") (class "Default")
      (node (ref "IC1") (pin "11") (pinfunction "PB5(ADCB5/TDI)_11") (pintype "bidirectional"))
      (node (ref "X3") (pin "9") (pinfunction "TDI/MOSI_9") (pintype "bidirectional"))
    )
    (net (code "43") (name "/TDO") (class "Default")
      (node (ref "IC1") (pin "13") (pinfunction "PB7(ADCB7/TDO)_13") (pintype "bidirectional"))
      (node (ref "IC1") (pin "56") (pinfunction "PDI_DATA_56") (pintype "bidirectional"))
      (node (ref "X3") (pin "3") (pinfunction "TDO/MISO/PDI_D_3") (pintype "bidirectional"))
    )
    (net (code "44") (name "/TMS") (class "Default")
      (node (ref "IC1") (pin "10") (pinfunction "PB4(ADCB4/TMS)_10") (pintype "bidirectional"))
      (node (ref "X3") (pin "5") (pinfunction "TMS_5") (pintype "bidirectional"))
    )
    (net (code "45") (name "/TXCAN") (class "Default")
      (node (ref "IC5") (pin "6") (pinfunction "B2IN_6") (pintype "bidirectional"))
      (node (ref "U1") (pin "1") (pinfunction "TXCAN_1") (pintype "output"))
    )
    (net (code "46") (name "/TXD") (class "Default")
      (node (ref "IC1") (pin "29") (pinfunction "PD3(TXD0/OC0D)_29") (pintype "bidirectional"))
      (node (ref "JP1") (pin "5") (pinfunction "5_5") (pintype "passive"))
    )
    (net (code "47") (name "/TXDE") (class "Default")
      (node (ref "IC1") (pin "39") (pinfunction "PE3(TXD0/OC0D)_39") (pintype "bidirectional"))
      (node (ref "JP2") (pin "5") (pinfunction "5_5") (pintype "passive"))
    )
    (net (code "48") (name "/TXDF") (class "Default")
      (node (ref "IC1") (pin "49") (pinfunction "PF3(TXD0/OC0D)_49") (pintype "bidirectional"))
      (node (ref "JP2") (pin "1") (pinfunction "1_1") (pintype "passive"))
    )
    (net (code "49") (name "/VBAT") (class "Default")
      (node (ref "IC1") (pin "51") (pinfunction "V_BAT_51") (pintype "input"))
      (node (ref "R24") (pin "1") (pinfunction "1_1") (pintype "passive"))
    )
    (net (code "50") (name "/VCC3V3") (class "Default")
      (node (ref "C1") (pin "1") (pinfunction "1_1") (pintype "passive"))
      (node (ref "C15") (pin "P") (pinfunction "+_P") (pintype "passive"))
      (node (ref "C16") (pin "1") (pinfunction "1_1") (pintype "passive"))
      (node (ref "C18") (pin "1") (pinfunction "1_1") (pintype "passive"))
      (node (ref "C22") (pin "1") (pinfunction "1_1") (pintype "passive"))
      (node (ref "C24") (pin "1") (pinfunction "1_1") (pintype "passive"))
      (node (ref "C26") (pin "1") (pinfunction "1_1") (pintype "passive"))
      (node (ref "C27") (pin "1") (pinfunction "1_1") (pintype "passive"))
      (node (ref "C28") (pin "1") (pinfunction "1_1") (pintype "passive"))
      (node (ref "C29") (pin "1") (pinfunction "1_1") (pintype "passive"))
      (node (ref "C30") (pin "1") (pinfunction "1_1") (pintype "passive"))
      (node (ref "C6") (pin "1") (pinfunction "1_1") (pintype "passive"))
      (node (ref "C7") (pin "1") (pinfunction "1_1") (pintype "passive"))
      (node (ref "D7") (pin "A") (pinfunction "A_A") (pintype "bidirectional"))
      (node (ref "IC1") (pin "15") (pinfunction "VCC1_15") (pintype "power_in"))
      (node (ref "IC1") (pin "25") (pinfunction "VCC2_25") (pintype "power_in"))
      (node (ref "IC1") (pin "35") (pinfunction "VCC3_35") (pintype "bidirectional"))
      (node (ref "IC1") (pin "45") (pinfunction "VCC4_45") (pintype "input"))
      (node (ref "IC1") (pin "53") (pinfunction "VCC5_53") (pintype "bidirectional"))
      (node (ref "IC3") (pin "4") (pinfunction "VCC_4") (pintype "power_in"))
      (node (ref "IC5") (pin "8") (pinfunction "VCC2_8") (pintype "bidirectional"))
      (node (ref "IC7") (pin "13") (pinfunction "I_13") (pintype "input"))
      (node (ref "IC7") (pin "14") (pinfunction "VCC_14") (pintype "power_in"))
      (node (ref "IC8") (pin "8") (pinfunction "V+_8") (pintype "power_in"))
      (node (ref "IC9") (pin "14") (pinfunction "VDD_14") (pintype "bidirectional"))
      (node (ref "JP1") (pin "10") (pinfunction "10_10") (pintype "passive"))
      (node (ref "JP2") (pin "10") (pinfunction "10_10") (pintype "passive"))
      (node (ref "L6") (pin "2") (pinfunction "2_2") (pintype "passive"))
      (node (ref "LD2") (pin "A") (pinfunction "A_A") (pintype "passive"))
      (node (ref "R1") (pin "2") (pinfunction "2_2") (pintype "passive"))
      (node (ref "R10") (pin "2") (pinfunction "2_2") (pintype "passive"))
      (node (ref "R13") (pin "2") (pinfunction "2_2") (pintype "passive"))
      (node (ref "R23") (pin "1") (pinfunction "1_1") (pintype "passive"))
      (node (ref "R24") (pin "2") (pinfunction "2_2") (pintype "passive"))
      (node (ref "R9") (pin "1") (pinfunction "1_1") (pintype "passive"))
      (node (ref "SV1") (pin "1") (pinfunction "A_1") (pintype "bidirectional"))
      (node (ref "SV2") (pin "1") (pinfunction "A_1") (pintype "bidirectional"))
      (node (ref "SV3") (pin "1") (pinfunction "A_1") (pintype "bidirectional"))
      (node (ref "T1") (pin "3") (pinfunction "+VIN_3") (pintype "power_in"))
      (node (ref "U1") (pin "18") (pinfunction "VDD_18") (pintype "power_in"))
      (node (ref "U4") (pin "4") (pinfunction "VOUT_4") (pintype "output"))
      (node (ref "X3") (pin "4") (pinfunction "V_TARGET_4") (pintype "bidirectional"))
      (node (ref "X3") (pin "7") (pinfunction "NA1_7") (pintype "bidirectional"))
    )
    (net (code "51") (name "/VCC5V") (class "Default")
      (node (ref "C11") (pin "P$2") (pinfunction "+_P$2") (pintype "passive"))
      (node (ref "C12") (pin "1") (pinfunction "1_1") (pintype "passive"))
      (node (ref "C13") (pin "1") (pinfunction "1_1") (pintype "passive"))
      (node (ref "C23") (pin "1") (pinfunction "1_1") (pintype "passive"))
      (node (ref "IC2") (pin "FEEDBACK") (pinfunction "FB_FEEDBACK") (pintype "input"))
      (node (ref "L2") (pin "2") (pinfunction "2_2") (pintype "passive"))
      (node (ref "L3") (pin "1") (pinfunction "1_1") (pintype "passive"))
      (node (ref "L4") (pin "1") (pinfunction "1_1") (pintype "passive"))
      (node (ref "L5") (pin "1") (pinfunction "1_1") (pintype "passive"))
      (node (ref "U3") (pin "8") (pinfunction "VDD_8") (pintype "power_in"))
      (node (ref "U4") (pin "1") (pinfunction "~{SHDN}_1") (pintype "bidirectional"))
      (node (ref "U4") (pin "2") (pinfunction "VIN_2") (pintype "input"))
    )
    (net (code "52") (name "/VCC_A") (class "Default")
      (node (ref "D4") (pin "P$2") (pinfunction "A_P$2") (pintype "bidirectional"))
      (node (ref "F1") (pin "P$2") (pinfunction "2_P$2") (pintype "passive"))
    )
    (net (code "53") (name "/VCC_B") (class "Default")
      (node (ref "D5") (pin "P$2") (pinfunction "A_P$2") (pintype "bidirectional"))
      (node (ref "F2") (pin "P$2") (pinfunction "2_P$2") (pintype "passive"))
    )
    (net (code "54") (name "/V_BAT") (class "Default")
      (node (ref "B2") (pin "P$1") (pinfunction "+_P$1") (pintype "passive"))
      (node (ref "D8") (pin "A") (pinfunction "A_A") (pintype "bidirectional"))
    )
    (net (code "55") (name "/V_IN") (class "Default")
      (node (ref "C14") (pin "P$2") (pinfunction "+_P$2") (pintype "passive"))
      (node (ref "D4") (pin "P$1") (pinfunction "C_P$1") (pintype "bidirectional"))
      (node (ref "D5") (pin "P$1") (pinfunction "C_P$1") (pintype "bidirectional"))
      (node (ref "D6") (pin "A") (pinfunction "A_A") (pintype "passive"))
      (node (ref "IC2") (pin "V_IN") (pinfunction "VIN_V_IN") (pintype "power_in"))
      (node (ref "J6") (pin "1") (pinfunction "P$1_1") (pintype "bidirectional"))
      (node (ref "K1") (pin "2") (pinfunction "2_2") (pintype "passive"))
      (node (ref "K2") (pin "3") (pinfunction "DS2_3") (pintype "passive"))
      (node (ref "LD1") (pin "2") (pinfunction "A_2") (pintype "bidirectional"))
      (node (ref "R18") (pin "1") (pinfunction "1_1") (pintype "passive"))
    )
    (net (code "56") (name "/~{RST}") (class "Default")
      (node (ref "IC1") (pin "57") (pinfunction "PDI_CLK/~{RESET}_57") (pintype "bidirectional"))
      (node (ref "R23") (pin "2") (pinfunction "2_2") (pintype "passive"))
      (node (ref "X3") (pin "6") (pinfunction "NSRST/RESET/PDI_C_6") (pintype "bidirectional"))
    )
    (net (code "57") (name "/~{SSD}") (class "Default")
      (node (ref "IC1") (pin "30") (pinfunction "PD4(~{SS}/OC1A)_30") (pintype "bidirectional"))
      (node (ref "JP1") (pin "4") (pinfunction "4_4") (pintype "passive"))
    )
    (net (code "58") (name "Net-(C10-Pad1)") (class "Default")
      (node (ref "C10") (pin "1") (pinfunction "1_1") (pintype "passive"))
      (node (ref "D2") (pin "C") (pinfunction "C_C") (pintype "passive"))
      (node (ref "R2") (pin "2") (pinfunction "2_2") (pintype "passive"))
      (node (ref "R3") (pin "1") (pinfunction "1_1") (pintype "passive"))
    )
    (net (code "59") (name "Net-(C17-+)") (class "Default")
      (node (ref "B1") (pin "+") (pinfunction "+_+") (pintype "passive"))
      (node (ref "C17") (pin "P") (pinfunction "+_P") (pintype "passive"))
      (node (ref "IC8") (pin "3") (pinfunction "+IN_3") (pintype "input"))
      (node (ref "R14") (pin "1") (pinfunction "1_1") (pintype "passive"))
    )
    (net (code "60") (name "Net-(C19-+)") (class "Default")
      (node (ref "C19") (pin "P") (pinfunction "+_P") (pintype "passive"))
      (node (ref "J1") (pin "1") (pinfunction "P$1_1") (pintype "bidirectional"))
      (node (ref "L3") (pin "2") (pinfunction "2_2") (pintype "passive"))
    )
    (net (code "61") (name "Net-(C20-+)") (class "Default")
      (node (ref "C20") (pin "P") (pinfunction "+_P") (pintype "passive"))
      (node (ref "J2") (pin "1") (pinfunction "P$1_1") (pintype "bidirectional"))
      (node (ref "L4") (pin "2") (pinfunction "2_2") (pintype "passive"))
    )
    (net (code "62") (name "Net-(C21-+)") (class "Default")
      (node (ref "C21") (pin "P") (pinfunction "+_P") (pintype "passive"))
      (node (ref "J3") (pin "1") (pinfunction "P$1_1") (pintype "bidirectional"))
      (node (ref "L5") (pin "2") (pinfunction "2_2") (pintype "passive"))
    )
    (net (code "63") (name "Net-(D1-PadC)") (class "Default")
      (node (ref "D1") (pin "C") (pinfunction "C_C") (pintype "passive"))
      (node (ref "R2") (pin "1") (pinfunction "1_1") (pintype "passive"))
    )
    (net (code "64") (name "Net-(D3-C)") (class "Default")
      (node (ref "D3") (pin "P$1") (pinfunction "C_P$1") (pintype "bidirectional"))
      (node (ref "IC2") (pin "OUTPUT") (pinfunction "VOUT_OUTPUT") (pintype "power_in"))
      (node (ref "L2") (pin "1") (pinfunction "1_1") (pintype "passive"))
    )
    (net (code "65") (name "Net-(IC1-PA1(ADCA1))") (class "Default")
      (node (ref "IC1") (pin "63") (pinfunction "PA1(ADCA1)_63") (pintype "bidirectional"))
      (node (ref "R25") (pin "2") (pinfunction "2_2") (pintype "passive"))
    )
    (net (code "66") (name "Net-(IC1-PA2(ADCA2))") (class "Default")
      (node (ref "IC1") (pin "64") (pinfunction "PA2(ADCA2)_64") (pintype "bidirectional"))
      (node (ref "R26") (pin "2") (pinfunction "2_2") (pintype "passive"))
    )
    (net (code "67") (name "Net-(IC1-PA3(ADCA3))") (class "Default")
      (node (ref "IC1") (pin "1") (pinfunction "PA3(ADCA3)_1") (pintype "bidirectional"))
      (node (ref "R27") (pin "2") (pinfunction "2_2") (pintype "passive"))
    )
    (net (code "68") (name "Net-(IC1-PR0(XTAL2))") (class "Default")
      (node (ref "C32") (pin "1") (pinfunction "1_1") (pintype "passive"))
      (node (ref "IC1") (pin "58") (pinfunction "PR0(XTAL2)_58") (pintype "bidirectional"))
      (node (ref "XT2") (pin "1") (pinfunction "1_1") (pintype "passive"))
    )
    (net (code "69") (name "Net-(IC1-PR1(XTAL1))") (class "Default")
      (node (ref "C33") (pin "1") (pinfunction "1_1") (pintype "passive"))
      (node (ref "IC1") (pin "59") (pinfunction "PR1(XTAL1)_59") (pintype "bidirectional"))
      (node (ref "XT2") (pin "3") (pinfunction "3_3") (pintype "passive"))
    )
    (net (code "70") (name "Net-(IC4-RTC_VDD)") (class "Default")
      (node (ref "C25") (pin "1") (pinfunction "1_1") (pintype "passive"))
      (node (ref "D7") (pin "K") (pinfunction "K_K") (pintype "bidirectional"))
      (node (ref "D8") (pin "K") (pinfunction "K_K") (pintype "bidirectional"))
      (node (ref "IC4") (pin "3") (pinfunction "RTC_VDD_3") (pintype "bidirectional"))
    )
    (net (code "71") (name "Net-(IC5-A1IN)") (class "Default")
      (node (ref "IC5") (pin "2") (pinfunction "A1IN_2") (pintype "bidirectional"))
      (node (ref "U2") (pin "4") (pinfunction "RXD_4") (pintype "bidirectional"))
    )
    (net (code "72") (name "Net-(IC5-A2OUT)") (class "Default")
      (node (ref "IC5") (pin "3") (pinfunction "A2OUT_3") (pintype "bidirectional"))
      (node (ref "U2") (pin "1") (pinfunction "TXD_1") (pintype "bidirectional"))
    )
    (net (code "73") (name "Net-(IC6-ANODE)") (class "Default")
      (node (ref "IC6") (pin "1") (pinfunction "ANODE_1") (pintype "passive"))
      (node (ref "R3") (pin "2") (pinfunction "2_2") (pintype "passive"))
    )
    (net (code "74") (name "Net-(IC6-C)") (class "Default")
      (node (ref "IC6") (pin "4") (pinfunction "C_4") (pintype "passive"))
      (node (ref "IC7") (pin "3") (pinfunction "I_3") (pintype "input"))
      (node (ref "R9") (pin "2") (pinfunction "2_2") (pintype "passive"))
    )
    (net (code "75") (name "Net-(IC6-KATODE)") (class "Default")
      (node (ref "C10") (pin "2") (pinfunction "2_2") (pintype "passive"))
      (node (ref "D2") (pin "A") (pinfunction "A_A") (pintype "passive"))
      (node (ref "IC6") (pin "2") (pinfunction "KATODE_2") (pintype "passive"))
      (node (ref "K1") (pin "S2") (pinfunction "S_S2") (pintype "passive"))
      (node (ref "X1") (pin "PIN6") (pinfunction "PIN6_PIN6") (pintype "bidirectional"))
    )
    (net (code "76") (name "Net-(IC7B-O)") (class "Default")
      (node (ref "IC7") (pin "10") (pinfunction "O_10") (pintype "output"))
      (node (ref "R28") (pin "1") (pinfunction "1_1") (pintype "passive"))
    )
    (net (code "77") (name "Net-(IC7C-I)") (class "Default")
      (node (ref "IC7") (pin "6") (pinfunction "O_6") (pintype "output"))
      (node (ref "IC7") (pin "9") (pinfunction "I_9") (pintype "input"))
      (node (ref "R12") (pin "1") (pinfunction "1_1") (pintype "passive"))
    )
    (net (code "78") (name "Net-(IC7C-O)") (class "Default")
      (node (ref "IC7") (pin "8") (pinfunction "O_8") (pintype "output"))
      (node (ref "R11") (pin "1") (pinfunction "1_1") (pintype "passive"))
    )
    (net (code "79") (name "Net-(IC7D-O)") (class "Default")
      (node (ref "IC7") (pin "2") (pinfunction "O_2") (pintype "output"))
      (node (ref "R8") (pin "1") (pinfunction "1_1") (pintype "passive"))
    )
    (net (code "80") (name "Net-(IC8B--IN)") (class "Default")
      (node (ref "IC8") (pin "6") (pinfunction "-IN_6") (pintype "input"))
      (node (ref "IC8") (pin "7") (pinfunction "OUT_7") (pintype "output"))
    )
    (net (code "81") (name "Net-(IC9-A0)") (class "Default")
      (node (ref "IC9") (pin "11") (pinfunction "A0_11") (pintype "bidirectional"))
      (node (ref "SV1") (pin "2") (pinfunction "W_2") (pintype "bidirectional"))
    )
    (net (code "82") (name "Net-(IC9-A1)") (class "Default")
      (node (ref "IC9") (pin "10") (pinfunction "A1_10") (pintype "bidirectional"))
      (node (ref "SV2") (pin "2") (pinfunction "W_2") (pintype "bidirectional"))
    )
    (net (code "83") (name "Net-(IC9-A2)") (class "Default")
      (node (ref "IC9") (pin "9") (pinfunction "A2_9") (pintype "bidirectional"))
      (node (ref "SV3") (pin "2") (pinfunction "W_2") (pintype "bidirectional"))
    )
    (net (code "84") (name "Net-(IC9-HA)") (class "Default")
      (node (ref "IC9") (pin "1") (pinfunction "HA_1") (pintype "bidirectional"))
      (node (ref "J4") (pin "3") (pinfunction "P$3_3") (pintype "bidirectional"))
    )
    (net (code "85") (name "Net-(IC9-HB)") (class "Default")
      (node (ref "IC9") (pin "4") (pinfunction "HB_4") (pintype "bidirectional"))
      (node (ref "J5") (pin "3") (pinfunction "P$3_3") (pintype "bidirectional"))
    )
    (net (code "86") (name "Net-(IC9-LA)") (class "Default")
      (node (ref "IC9") (pin "3") (pinfunction "LA_3") (pintype "bidirectional"))
      (node (ref "J4") (pin "1") (pinfunction "P$1_1") (pintype "bidirectional"))
    )
    (net (code "87") (name "Net-(IC9-LB)") (class "Default")
      (node (ref "IC9") (pin "6") (pinfunction "LB_6") (pintype "bidirectional"))
      (node (ref "J5") (pin "1") (pinfunction "P$1_1") (pintype "bidirectional"))
    )
    (net (code "88") (name "Net-(IC9-WA)") (class "Default")
      (node (ref "IC9") (pin "2") (pinfunction "WA_2") (pintype "bidirectional"))
      (node (ref "J4") (pin "2") (pinfunction "P$2_2") (pintype "bidirectional"))
    )
    (net (code "89") (name "Net-(IC9-WB)") (class "Default")
      (node (ref "IC9") (pin "5") (pinfunction "WB_5") (pintype "bidirectional"))
      (node (ref "J5") (pin "2") (pinfunction "P$2_2") (pintype "bidirectional"))
    )
    (net (code "90") (name "Net-(J6-P$3)") (class "Default")
      (node (ref "J6") (pin "3") (pinfunction "P$3_3") (pintype "bidirectional"))
      (node (ref "Q2") (pin "5") (pinfunction "D_5") (pintype "passive"))
      (node (ref "Q2") (pin "6") (pinfunction "D_6") (pintype "passive"))
      (node (ref "Q2") (pin "7") (pinfunction "D_7") (pintype "passive"))
      (node (ref "Q2") (pin "8") (pinfunction "D_8") (pintype "passive"))
      (node (ref "Q2") (pin "9") (pinfunction "D_9") (pintype "passive"))
    )
    (net (code "91") (name "Net-(K1B-O)") (class "Default")
      (node (ref "K1") (pin "O1") (pinfunction "O_O1") (pintype "passive"))
      (node (ref "X1") (pin "PIN4") (pinfunction "PIN4_PIN4") (pintype "bidirectional"))
    )
    (net (code "92") (name "Net-(K1B-P)") (class "Default")
      (node (ref "K1") (pin "P1") (pinfunction "P_P1") (pintype "passive"))
      (node (ref "X1") (pin "PIN2") (pinfunction "PIN2_PIN2") (pintype "bidirectional"))
    )
    (net (code "93") (name "Net-(K1B-S)") (class "Default")
      (node (ref "D1") (pin "A") (pinfunction "A_A") (pintype "passive"))
      (node (ref "K1") (pin "S1") (pinfunction "S_S1") (pintype "passive"))
      (node (ref "X1") (pin "PIN5") (pinfunction "PIN5_PIN5") (pintype "bidirectional"))
    )
    (net (code "94") (name "Net-(K1C-O)") (class "Default")
      (node (ref "K1") (pin "O2") (pinfunction "O_O2") (pintype "passive"))
      (node (ref "X1") (pin "PIN3") (pinfunction "PIN3_PIN3") (pintype "bidirectional"))
    )
    (net (code "95") (name "Net-(K1C-P)") (class "Default")
      (node (ref "K1") (pin "P2") (pinfunction "P_P2") (pintype "passive"))
      (node (ref "X1") (pin "PIN1") (pinfunction "PIN1_PIN1") (pintype "bidirectional"))
    )
    (net (code "96") (name "Net-(K2-A)") (class "Default")
      (node (ref "K2") (pin "1") (pinfunction "A_1") (pintype "passive"))
      (node (ref "R11") (pin "2") (pinfunction "2_2") (pintype "passive"))
      (node (ref "R12") (pin "2") (pinfunction "2_2") (pintype "passive"))
    )
    (net (code "97") (name "Net-(L1-3)") (class "Default")
      (node (ref "L1") (pin "P$3") (pinfunction "3_P$3") (pintype "passive"))
      (node (ref "U2") (pin "7") (pinfunction "CANH_7") (pintype "bidirectional"))
    )
    (net (code "98") (name "Net-(L1-4)") (class "Default")
      (node (ref "L1") (pin "P$4") (pinfunction "4_P$4") (pintype "passive"))
      (node (ref "U2") (pin "6") (pinfunction "CANL_6") (pintype "bidirectional"))
    )
    (net (code "99") (name "Net-(LD1-K)") (class "Default")
      (node (ref "LD1") (pin "1") (pinfunction "K_1") (pintype "bidirectional"))
      (node (ref "R6") (pin "2") (pinfunction "2_2") (pintype "passive"))
    )
    (net (code "100") (name "Net-(LD2-BC)") (class "Default")
      (node (ref "LD2") (pin "B") (pinfunction "BC_B") (pintype "passive"))
      (node (ref "R25") (pin "1") (pinfunction "1_1") (pintype "passive"))
    )
    (net (code "101") (name "Net-(LD2-GC)") (class "Default")
      (node (ref "LD2") (pin "G") (pinfunction "GC_G") (pintype "passive"))
      (node (ref "R27") (pin "1") (pinfunction "1_1") (pintype "passive"))
    )
    (net (code "102") (name "Net-(LD2-RC)") (class "Default")
      (node (ref "LD2") (pin "R") (pinfunction "RC_R") (pintype "passive"))
      (node (ref "R26") (pin "1") (pinfunction "1_1") (pintype "passive"))
    )
    (net (code "103") (name "Net-(Q1-D)") (class "Default")
      (node (ref "D6") (pin "C") (pinfunction "C_C") (pintype "passive"))
      (node (ref "K1") (pin "1") (pinfunction "1_1") (pintype "passive"))
      (node (ref "Q1") (pin "3") (pinfunction "D_3") (pintype "passive"))
      (node (ref "R6") (pin "1") (pinfunction "1_1") (pintype "passive"))
    )
    (net (code "104") (name "Net-(Q1-G)") (class "Default")
      (node (ref "Q1") (pin "1") (pinfunction "G_1") (pintype "passive"))
      (node (ref "R7") (pin "2") (pinfunction "2_2") (pintype "passive"))
      (node (ref "R8") (pin "2") (pinfunction "2_2") (pintype "passive"))
    )
    (net (code "105") (name "Net-(Q2-G)") (class "Default")
      (node (ref "Q2") (pin "4") (pinfunction "G_4") (pintype "passive"))
      (node (ref "R28") (pin "2") (pinfunction "2_2") (pintype "passive"))
      (node (ref "R29") (pin "2") (pinfunction "2_2") (pintype "passive"))
    )
    (net (code "106") (name "Net-(U1-OSC1)") (class "Default")
      (node (ref "C9") (pin "1") (pinfunction "1_1") (pintype "passive"))
      (node (ref "U1") (pin "8") (pinfunction "OSC1_8") (pintype "input"))
      (node (ref "XT1") (pin "3") (pinfunction "3_3") (pintype "passive"))
    )
    (net (code "107") (name "Net-(U1-OSC2)") (class "Default")
      (node (ref "C8") (pin "1") (pinfunction "1_1") (pintype "passive"))
      (node (ref "U1") (pin "7") (pinfunction "OSC2_7") (pintype "output"))
      (node (ref "XT1") (pin "1") (pinfunction "1_1") (pintype "passive"))
    )
    (net (code "108") (name "Net-(U3-AIN0)") (class "Default")
      (node (ref "R15") (pin "2") (pinfunction "2_2") (pintype "passive"))
      (node (ref "R19") (pin "2") (pinfunction "2_2") (pintype "passive"))
      (node (ref "U3") (pin "4") (pinfunction "AIN0_4") (pintype "input"))
    )
    (net (code "109") (name "Net-(U3-AIN1)") (class "Default")
      (node (ref "R16") (pin "2") (pinfunction "2_2") (pintype "passive"))
      (node (ref "R20") (pin "2") (pinfunction "2_2") (pintype "passive"))
      (node (ref "U3") (pin "5") (pinfunction "AIN1_5") (pintype "input"))
    )
    (net (code "110") (name "Net-(U3-AIN2)") (class "Default")
      (node (ref "R17") (pin "2") (pinfunction "2_2") (pintype "passive"))
      (node (ref "R21") (pin "2") (pinfunction "2_2") (pintype "passive"))
      (node (ref "U3") (pin "6") (pinfunction "AIN2_6") (pintype "input"))
    )
    (net (code "111") (name "Net-(U3-AIN3)") (class "Default")
      (node (ref "R18") (pin "2") (pinfunction "2_2") (pintype "passive"))
      (node (ref "R22") (pin "2") (pinfunction "2_2") (pintype "passive"))
      (node (ref "U3") (pin "7") (pinfunction "AIN3_7") (pintype "input"))
    )
    (net (code "112") (name "unconnected-(IC1-PA4(ADCA4)-Pad2)") (class "Default")
      (node (ref "IC1") (pin "2") (pinfunction "PA4(ADCA4)_2") (pintype "bidirectional"))
    )
    (net (code "113") (name "unconnected-(IC1-PA5(ADCA5)-Pad3)") (class "Default")
      (node (ref "IC1") (pin "3") (pinfunction "PA5(ADCA5)_3") (pintype "bidirectional"))
    )
    (net (code "114") (name "unconnected-(IC1-PC3(TXD0{slash}OC0D)-Pad19)") (class "Default")
      (node (ref "IC1") (pin "19") (pinfunction "PC3(TXD0/OC0D)_19") (pintype "bidirectional"))
    )
    (net (code "115") (name "unconnected-(IC1-PC4(~{SS}{slash}OC1A)-Pad20)") (class "Default")
      (node (ref "IC1") (pin "20") (pinfunction "PC4(~{SS}/OC1A)_20") (pintype "bidirectional"))
    )
    (net (code "116") (name "unconnected-(IC1-PF0(OC0A)-Pad46)") (class "Default")
      (node (ref "IC1") (pin "46") (pinfunction "PF0(OC0A)_46") (pintype "bidirectional"))
    )
    (net (code "117") (name "unconnected-(IC1-PF1(XCK0{slash}OC0B)-Pad47)") (class "Default")
      (node (ref "IC1") (pin "47") (pinfunction "PF1(XCK0/OC0B)_47") (pintype "bidirectional"))
    )
    (net (code "118") (name "unconnected-(IC1-PF4(OC0A)-Pad50)") (class "Default")
      (node (ref "IC1") (pin "50") (pinfunction "PF4(OC0A)_50") (pintype "bidirectional"))
    )
    (net (code "119") (name "unconnected-(IC1-PF6-Pad54)") (class "Default")
      (node (ref "IC1") (pin "54") (pinfunction "PF6_54") (pintype "bidirectional"))
    )
    (net (code "120") (name "unconnected-(IC1-PF7-Pad55)") (class "Default")
      (node (ref "IC1") (pin "55") (pinfunction "PF7_55") (pintype "bidirectional"))
    )
    (net (code "121") (name "unconnected-(IC1-TOSC1-Pad42)") (class "Default")
      (node (ref "IC1") (pin "42") (pinfunction "TOSC1_42") (pintype "input"))
    )
    (net (code "122") (name "unconnected-(IC1-TOSC2-Pad43)") (class "Default")
      (node (ref "IC1") (pin "43") (pinfunction "TOSC2_43") (pintype "input"))
    )
    (net (code "123") (name "unconnected-(IC4-CLKO-Pad2)") (class "Default")
      (node (ref "IC4") (pin "2") (pinfunction "CLKO_2") (pintype "bidirectional"))
    )
    (net (code "124") (name "unconnected-(IC4-CLKOE-Pad4)") (class "Default")
      (node (ref "IC4") (pin "4") (pinfunction "CLKOE_4") (pintype "bidirectional"))
    )
    (net (code "125") (name "unconnected-(IC4-EVI-Pad7)") (class "Default")
      (node (ref "IC4") (pin "7") (pinfunction "EVI_7") (pintype "bidirectional"))
    )
    (net (code "126") (name "unconnected-(IC4-~{INT}-Pad6)") (class "Default")
      (node (ref "IC4") (pin "6") (pinfunction "~{INT}_6") (pintype "bidirectional"))
    )
    (net (code "127") (name "unconnected-(IC7A-O-Pad12)") (class "Default")
      (node (ref "IC7") (pin "12") (pinfunction "O_12") (pintype "output"))
    )
    (net (code "128") (name "unconnected-(IC8B-+IN-Pad5)") (class "Default")
      (node (ref "IC8") (pin "5") (pinfunction "+IN_5") (pintype "input"))
    )
    (net (code "129") (name "unconnected-(J6-P$2-Pad2)") (class "Default")
      (node (ref "J6") (pin "2") (pinfunction "P$2_2") (pintype "bidirectional"))
    )
    (net (code "130") (name "unconnected-(T1-1_NC-Pad14)") (class "Default")
      (node (ref "T1") (pin "14") (pinfunction "1_NC_14") (pintype "passive"))
    )
    (net (code "131") (name "unconnected-(U$1-PadSC1)") (class "Default")
      (node (ref "U$1") (pin "SC1") (pinfunction "SC1_SC1") (pintype "bidirectional"))
    )
    (net (code "132") (name "unconnected-(U$1-PadSC2)") (class "Default")
      (node (ref "U$1") (pin "SC2") (pinfunction "SC2_SC2") (pintype "bidirectional"))
    )
    (net (code "133") (name "unconnected-(U$1-PadSC3)") (class "Default")
      (node (ref "U$1") (pin "SC3") (pinfunction "SC3_SC3") (pintype "bidirectional"))
    )
    (net (code "134") (name "unconnected-(U$1-PadSC4)") (class "Default")
      (node (ref "U$1") (pin "SC4") (pinfunction "SC4_SC4") (pintype "bidirectional"))
    )
    (net (code "135") (name "unconnected-(U1-CLKOUT{slash}SOF-Pad3)") (class "Default")
      (node (ref "U1") (pin "3") (pinfunction "CLKOUT/SOF_3") (pintype "output"))
    )
    (net (code "136") (name "unconnected-(U1-~{RX0BF}-Pad11)") (class "Default")
      (node (ref "U1") (pin "11") (pinfunction "~{RX0BF}_11") (pintype "output"))
    )
    (net (code "137") (name "unconnected-(U1-~{RX1BF}-Pad10)") (class "Default")
      (node (ref "U1") (pin "10") (pinfunction "~{RX1BF}_10") (pintype "output"))
    )
    (net (code "138") (name "unconnected-(U1-~{TX0RTS}-Pad4)") (class "Default")
      (node (ref "U1") (pin "4") (pinfunction "~{TX0RTS}_4") (pintype "input"))
    )
    (net (code "139") (name "unconnected-(U1-~{TX1RTS}-Pad5)") (class "Default")
      (node (ref "U1") (pin "5") (pinfunction "~{TX1RTS}_5") (pintype "input"))
    )
    (net (code "140") (name "unconnected-(U1-~{TX2RTS}-Pad6)") (class "Default")
      (node (ref "U1") (pin "6") (pinfunction "~{TX2RTS}_6") (pintype "input"))
    )
    (net (code "141") (name "unconnected-(U2-VREF-Pad5)") (class "Default")
      (node (ref "U2") (pin "5") (pinfunction "VREF_5") (pintype "bidirectional"))
    )
    (net (code "142") (name "unconnected-(U3-ALERT{slash}RDY-Pad2)") (class "Default")
      (node (ref "U3") (pin "2") (pinfunction "ALERT/RDY_2") (pintype "input"))
    )
    (net (code "143") (name "unconnected-(U4-PWRGD-Pad5)") (class "Default")
      (node (ref "U4") (pin "5") (pinfunction "PWRGD_5") (pintype "bidirectional"))
    )
    (net (code "144") (name "unconnected-(X3-NTRST-Pad8)") (class "Default")
      (node (ref "X3") (pin "8") (pinfunction "NTRST_8") (pintype "bidirectional"))
    )
  )
)
